# TromboneTutor.net
KiCad netlist of a schematic drawn in EAGLE
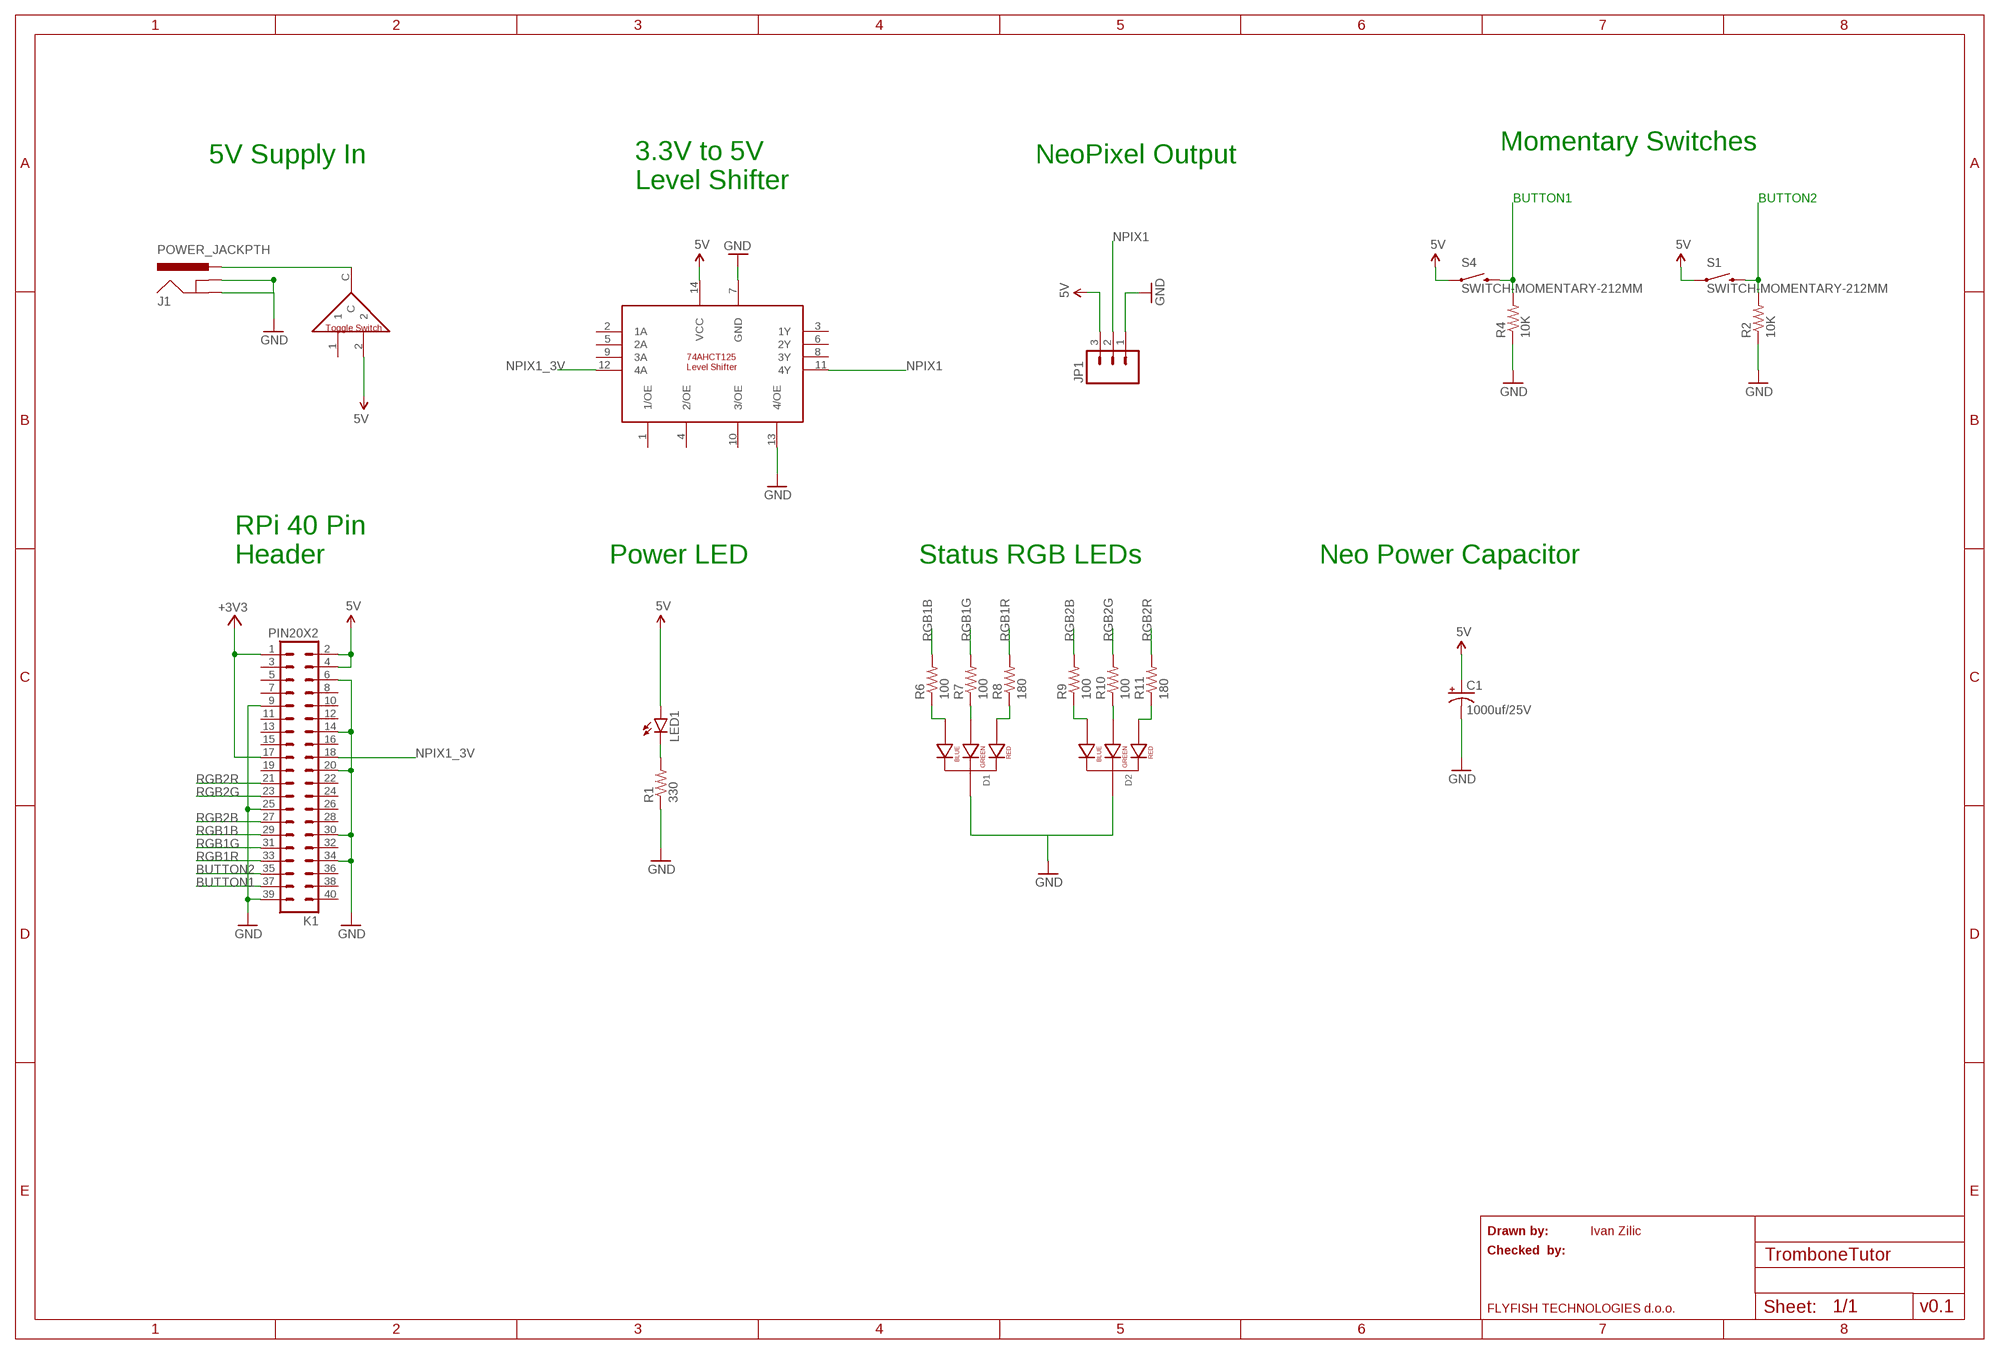
[diagram p0: schematic, sheet 1]

(export (version "E")
  (design (tool "Eeschema 10.0.6"))
  (components
    (comp (ref "C1")
      (value "1000uf/25V")
      (footprint "eagle-import:CPOL-RADIAL-1000UF-25V-KIT")
      (libsource (lib "eagle-import") (part "1000UF-25V(PTH)KIT"))
    )
    (comp (ref "D1")
      (value "LED-RGB-CC-THRUDIFFUSE")
      (footprint "eagle-import:LED-RGB-THRU")
      (libsource (lib "eagle-import") (part "LED-RGB-CC-THRUDIFFUSE"))
    )
    (comp (ref "D2")
      (value "LED-RGB-CC-THRUDIFFUSE")
      (footprint "eagle-import:LED-RGB-THRU")
      (libsource (lib "eagle-import") (part "LED-RGB-CC-THRUDIFFUSE"))
    )
    (comp (ref "J1")
      (value "POWER_JACKPTH")
      (footprint "eagle-import:POWER_JACK_PTH")
      (libsource (lib "eagle-import") (part "POWER_JACKPTH"))
    )
    (comp (ref "JP1")
      (value "M03PTH")
      (footprint "eagle-import:1X03")
      (libsource (lib "eagle-import") (part "M03PTH"))
    )
    (comp (ref "K1")
      (value "PIN20X2")
      (footprint "eagle-import:PIN_20X2")
      (libsource (lib "eagle-import") (part "PIN20X2"))
    )
    (comp (ref "LED1")
      (value "LED5MM")
      (footprint "eagle-import:LED5MM")
      (libsource (lib "eagle-import") (part "LED5MM"))
    )
    (comp (ref "R1")
      (value "330")
      (footprint "eagle-import:AXIAL-0.3")
      (libsource (lib "eagle-import") (part "RESISTORAXIAL-0.3"))
    )
    (comp (ref "R2")
      (value "10K")
      (footprint "eagle-import:AXIAL-0.3-KIT")
      (libsource (lib "eagle-import") (part "RESISTORKIT"))
    )
    (comp (ref "R4")
      (value "10K")
      (footprint "eagle-import:AXIAL-0.3-KIT")
      (libsource (lib "eagle-import") (part "RESISTORKIT"))
    )
    (comp (ref "R6")
      (value "100")
      (footprint "eagle-import:AXIAL-0.3")
      (libsource (lib "eagle-import") (part "RESISTORAXIAL-0.3"))
    )
    (comp (ref "R7")
      (value "100")
      (footprint "eagle-import:AXIAL-0.3")
      (libsource (lib "eagle-import") (part "RESISTORAXIAL-0.3"))
    )
    (comp (ref "R8")
      (value "180")
      (footprint "eagle-import:AXIAL-0.3")
      (libsource (lib "eagle-import") (part "RESISTORAXIAL-0.3"))
    )
    (comp (ref "R9")
      (value "100")
      (footprint "eagle-import:AXIAL-0.3")
      (libsource (lib "eagle-import") (part "RESISTORAXIAL-0.3"))
    )
    (comp (ref "R10")
      (value "100")
      (footprint "eagle-import:AXIAL-0.3")
      (libsource (lib "eagle-import") (part "RESISTORAXIAL-0.3"))
    )
    (comp (ref "R11")
      (value "180")
      (footprint "eagle-import:AXIAL-0.3")
      (libsource (lib "eagle-import") (part "RESISTORAXIAL-0.3"))
    )
    (comp (ref "S1")
      (value "SWITCH-MOMENTARY-212MM")
      (footprint "eagle-import:TACTILE-PTH-12MM")
      (libsource (lib "eagle-import") (part "SWITCH-MOMENTARY-212MM"))
    )
    (comp (ref "S4")
      (value "SWITCH-MOMENTARY-212MM")
      (footprint "eagle-import:TACTILE-PTH-12MM")
      (libsource (lib "eagle-import") (part "SWITCH-MOMENTARY-212MM"))
    )
    (comp (ref "U$1")
      (value "74AHCT125_LEVELSHIFT")
      (footprint "eagle-import:DIL14")
      (libsource (lib "eagle-import") (part "74AHCT125_LEVELSHIFT"))
    )
    (comp (ref "U$2")
      (value "TOGGLE_SWITCH_ESTORE")
      (footprint "eagle-import:TOGGLE_SWITCH_ESTORE")
      (libsource (lib "eagle-import") (part "TOGGLE_SWITCH_ESTORE"))
    )
  )
  (nets
    (net (code "1") (name "+3V3") (class "Default")
      (node (ref "K1") (pin "1") (pinfunction "1_1") (pintype "passive"))
      (node (ref "K1") (pin "17") (pinfunction "17_17") (pintype "passive"))
    )
    (net (code "2") (name "/BUTTON1") (class "Default")
      (node (ref "K1") (pin "37") (pinfunction "37_37") (pintype "passive"))
      (node (ref "R4") (pin "P$2") (pinfunction "2_P$2") (pintype "passive"))
      (node (ref "S4") (pin "3") (pinfunction "2_3") (pintype "passive"))
    )
    (net (code "3") (name "/BUTTON2") (class "Default")
      (node (ref "K1") (pin "35") (pinfunction "35_35") (pintype "passive"))
      (node (ref "R2") (pin "P$2") (pinfunction "2_P$2") (pintype "passive"))
      (node (ref "S1") (pin "3") (pinfunction "2_3") (pintype "passive"))
    )
    (net (code "4") (name "/NPIX1") (class "Default")
      (node (ref "JP1") (pin "2") (pinfunction "2_2") (pintype "passive"))
      (node (ref "U$1") (pin "11") (pinfunction "4Y_11") (pintype "bidirectional"))
    )
    (net (code "5") (name "/NPIX1_3V") (class "Default")
      (node (ref "K1") (pin "18") (pinfunction "18_18") (pintype "passive"))
      (node (ref "U$1") (pin "12") (pinfunction "4A_12") (pintype "bidirectional"))
    )
    (net (code "6") (name "/RGB1B") (class "Default")
      (node (ref "K1") (pin "29") (pinfunction "29_29") (pintype "passive"))
      (node (ref "R6") (pin "P$2") (pinfunction "2_P$2") (pintype "passive"))
    )
    (net (code "7") (name "/RGB1G") (class "Default")
      (node (ref "K1") (pin "31") (pinfunction "31_31") (pintype "passive"))
      (node (ref "R7") (pin "P$2") (pinfunction "2_P$2") (pintype "passive"))
    )
    (net (code "8") (name "/RGB1R") (class "Default")
      (node (ref "K1") (pin "33") (pinfunction "33_33") (pintype "passive"))
      (node (ref "R8") (pin "P$2") (pinfunction "2_P$2") (pintype "passive"))
    )
    (net (code "9") (name "/RGB2B") (class "Default")
      (node (ref "K1") (pin "27") (pinfunction "27_27") (pintype "passive"))
      (node (ref "R9") (pin "P$2") (pinfunction "2_P$2") (pintype "passive"))
    )
    (net (code "10") (name "/RGB2G") (class "Default")
      (node (ref "K1") (pin "23") (pinfunction "23_23") (pintype "passive"))
      (node (ref "R10") (pin "P$2") (pinfunction "2_P$2") (pintype "passive"))
    )
    (net (code "11") (name "/RGB2R") (class "Default")
      (node (ref "K1") (pin "21") (pinfunction "21_21") (pintype "passive"))
      (node (ref "R11") (pin "P$2") (pinfunction "2_P$2") (pintype "passive"))
    )
    (net (code "12") (name "5V") (class "Default")
      (node (ref "C1") (pin "+") (pinfunction "+_+") (pintype "passive"))
      (node (ref "JP1") (pin "3") (pinfunction "3_3") (pintype "passive"))
      (node (ref "K1") (pin "2") (pinfunction "2_2") (pintype "passive"))
      (node (ref "K1") (pin "4") (pinfunction "4_4") (pintype "passive"))
      (node (ref "LED1") (pin "A") (pinfunction "A_A") (pintype "passive"))
      (node (ref "S1") (pin "1") (pinfunction "1_1") (pintype "passive"))
      (node (ref "S4") (pin "1") (pinfunction "1_1") (pintype "passive"))
      (node (ref "U$1") (pin "14") (pinfunction "VCC_14") (pintype "bidirectional"))
      (node (ref "U$2") (pin "2") (pinfunction "2_2") (pintype "bidirectional"))
    )
    (net (code "13") (name "GND") (class "Default")
      (node (ref "C1") (pin "-") (pinfunction "-_-") (pintype "passive"))
      (node (ref "D1") (pin "2") (pinfunction "CATHODE_2") (pintype "bidirectional"))
      (node (ref "D2") (pin "2") (pinfunction "CATHODE_2") (pintype "bidirectional"))
      (node (ref "J1") (pin "GND") (pinfunction "GND_GND") (pintype "bidirectional"))
      (node (ref "J1") (pin "GNDBREAK") (pinfunction "GNDBREAK_GNDBREAK") (pintype "bidirectional"))
      (node (ref "JP1") (pin "1") (pinfunction "1_1") (pintype "passive"))
      (node (ref "K1") (pin "14") (pinfunction "14_14") (pintype "passive"))
      (node (ref "K1") (pin "20") (pinfunction "20_20") (pintype "passive"))
      (node (ref "K1") (pin "25") (pinfunction "25_25") (pintype "passive"))
      (node (ref "K1") (pin "30") (pinfunction "30_30") (pintype "passive"))
      (node (ref "K1") (pin "34") (pinfunction "34_34") (pintype "passive"))
      (node (ref "K1") (pin "39") (pinfunction "39_39") (pintype "passive"))
      (node (ref "K1") (pin "6") (pinfunction "6_6") (pintype "passive"))
      (node (ref "K1") (pin "9") (pinfunction "9_9") (pintype "passive"))
      (node (ref "R1") (pin "P$1") (pinfunction "1_P$1") (pintype "passive"))
      (node (ref "R2") (pin "P$1") (pinfunction "1_P$1") (pintype "passive"))
      (node (ref "R4") (pin "P$1") (pinfunction "1_P$1") (pintype "passive"))
      (node (ref "U$1") (pin "13") (pinfunction "4/OE_13") (pintype "bidirectional"))
      (node (ref "U$1") (pin "7") (pinfunction "GND_7") (pintype "bidirectional"))
    )
    (net (code "14") (name "Net-(D1-BLUE_CATHODE)") (class "Default")
      (node (ref "D1") (pin "4") (pinfunction "BLUE_CATHODE_4") (pintype "bidirectional"))
      (node (ref "R6") (pin "P$1") (pinfunction "1_P$1") (pintype "passive"))
    )
    (net (code "15") (name "Net-(D1-GREEN_CATHODE)") (class "Default")
      (node (ref "D1") (pin "3") (pinfunction "GREEN_CATHODE_3") (pintype "bidirectional"))
      (node (ref "R7") (pin "P$1") (pinfunction "1_P$1") (pintype "passive"))
    )
    (net (code "16") (name "Net-(D1-RED_CATHODE)") (class "Default")
      (node (ref "D1") (pin "1") (pinfunction "RED_CATHODE_1") (pintype "bidirectional"))
      (node (ref "R8") (pin "P$1") (pinfunction "1_P$1") (pintype "passive"))
    )
    (net (code "17") (name "Net-(D2-BLUE_CATHODE)") (class "Default")
      (node (ref "D2") (pin "4") (pinfunction "BLUE_CATHODE_4") (pintype "bidirectional"))
      (node (ref "R9") (pin "P$1") (pinfunction "1_P$1") (pintype "passive"))
    )
    (net (code "18") (name "Net-(D2-GREEN_CATHODE)") (class "Default")
      (node (ref "D2") (pin "3") (pinfunction "GREEN_CATHODE_3") (pintype "bidirectional"))
      (node (ref "R10") (pin "P$1") (pinfunction "1_P$1") (pintype "passive"))
    )
    (net (code "19") (name "Net-(D2-RED_CATHODE)") (class "Default")
      (node (ref "D2") (pin "1") (pinfunction "RED_CATHODE_1") (pintype "bidirectional"))
      (node (ref "R11") (pin "P$1") (pinfunction "1_P$1") (pintype "passive"))
    )
    (net (code "20") (name "Net-(J1-PadPWR)") (class "Default")
      (node (ref "J1") (pin "PWR") (pinfunction "PWR_PWR") (pintype "bidirectional"))
      (node (ref "U$2") (pin "C") (pinfunction "C_C") (pintype "bidirectional"))
    )
    (net (code "21") (name "Net-(LED1-C)") (class "Default")
      (node (ref "LED1") (pin "K") (pinfunction "C_K") (pintype "passive"))
      (node (ref "R1") (pin "P$2") (pinfunction "2_P$2") (pintype "passive"))
    )
    (net (code "22") (name "unconnected-(K1-Pad3)") (class "Default")
      (node (ref "K1") (pin "3") (pinfunction "3_3") (pintype "passive"))
    )
    (net (code "23") (name "unconnected-(K1-Pad5)") (class "Default")
      (node (ref "K1") (pin "5") (pinfunction "5_5") (pintype "passive"))
    )
    (net (code "24") (name "unconnected-(K1-Pad7)") (class "Default")
      (node (ref "K1") (pin "7") (pinfunction "7_7") (pintype "passive"))
    )
    (net (code "25") (name "unconnected-(K1-Pad8)") (class "Default")
      (node (ref "K1") (pin "8") (pinfunction "8_8") (pintype "passive"))
    )
    (net (code "26") (name "unconnected-(K1-Pad10)") (class "Default")
      (node (ref "K1") (pin "10") (pinfunction "10_10") (pintype "passive"))
    )
    (net (code "27") (name "unconnected-(K1-Pad11)") (class "Default")
      (node (ref "K1") (pin "11") (pinfunction "11_11") (pintype "passive"))
    )
    (net (code "28") (name "unconnected-(K1-Pad12)") (class "Default")
      (node (ref "K1") (pin "12") (pinfunction "12_12") (pintype "passive"))
    )
    (net (code "29") (name "unconnected-(K1-Pad13)") (class "Default")
      (node (ref "K1") (pin "13") (pinfunction "13_13") (pintype "passive"))
    )
    (net (code "30") (name "unconnected-(K1-Pad15)") (class "Default")
      (node (ref "K1") (pin "15") (pinfunction "15_15") (pintype "passive"))
    )
    (net (code "31") (name "unconnected-(K1-Pad16)") (class "Default")
      (node (ref "K1") (pin "16") (pinfunction "16_16") (pintype "passive"))
    )
    (net (code "32") (name "unconnected-(K1-Pad19)") (class "Default")
      (node (ref "K1") (pin "19") (pinfunction "19_19") (pintype "passive"))
    )
    (net (code "33") (name "unconnected-(K1-Pad22)") (class "Default")
      (node (ref "K1") (pin "22") (pinfunction "22_22") (pintype "passive"))
    )
    (net (code "34") (name "unconnected-(K1-Pad24)") (class "Default")
      (node (ref "K1") (pin "24") (pinfunction "24_24") (pintype "passive"))
    )
    (net (code "35") (name "unconnected-(K1-Pad26)") (class "Default")
      (node (ref "K1") (pin "26") (pinfunction "26_26") (pintype "passive"))
    )
    (net (code "36") (name "unconnected-(K1-Pad28)") (class "Default")
      (node (ref "K1") (pin "28") (pinfunction "28_28") (pintype "passive"))
    )
    (net (code "37") (name "unconnected-(K1-Pad32)") (class "Default")
      (node (ref "K1") (pin "32") (pinfunction "32_32") (pintype "passive"))
    )
    (net (code "38") (name "unconnected-(K1-Pad36)") (class "Default")
      (node (ref "K1") (pin "36") (pinfunction "36_36") (pintype "passive"))
    )
    (net (code "39") (name "unconnected-(K1-Pad38)") (class "Default")
      (node (ref "K1") (pin "38") (pinfunction "38_38") (pintype "passive"))
    )
    (net (code "40") (name "unconnected-(K1-Pad40)") (class "Default")
      (node (ref "K1") (pin "40") (pinfunction "40_40") (pintype "passive"))
    )
    (net (code "41") (name "unconnected-(U$1-1A-Pad2)") (class "Default")
      (node (ref "U$1") (pin "2") (pinfunction "1A_2") (pintype "bidirectional"))
    )
    (net (code "42") (name "unconnected-(U$1-1Y-Pad3)") (class "Default")
      (node (ref "U$1") (pin "3") (pinfunction "1Y_3") (pintype "bidirectional"))
    )
    (net (code "43") (name "unconnected-(U$1-1{slash}OE-Pad1)") (class "Default")
      (node (ref "U$1") (pin "1") (pinfunction "1/OE_1") (pintype "bidirectional"))
    )
    (net (code "44") (name "unconnected-(U$1-2A-Pad5)") (class "Default")
      (node (ref "U$1") (pin "5") (pinfunction "2A_5") (pintype "bidirectional"))
    )
    (net (code "45") (name "unconnected-(U$1-2Y-Pad6)") (class "Default")
      (node (ref "U$1") (pin "6") (pinfunction "2Y_6") (pintype "bidirectional"))
    )
    (net (code "46") (name "unconnected-(U$1-2{slash}OE-Pad4)") (class "Default")
      (node (ref "U$1") (pin "4") (pinfunction "2/OE_4") (pintype "bidirectional"))
    )
    (net (code "47") (name "unconnected-(U$1-3A-Pad9)") (class "Default")
      (node (ref "U$1") (pin "9") (pinfunction "3A_9") (pintype "bidirectional"))
    )
    (net (code "48") (name "unconnected-(U$1-3Y-Pad8)") (class "Default")
      (node (ref "U$1") (pin "8") (pinfunction "3Y_8") (pintype "bidirectional"))
    )
    (net (code "49") (name "unconnected-(U$1-3{slash}OE-Pad10)") (class "Default")
      (node (ref "U$1") (pin "10") (pinfunction "3/OE_10") (pintype "bidirectional"))
    )
    (net (code "50") (name "unconnected-(U$2-Pad1)") (class "Default")
      (node (ref "U$2") (pin "1") (pinfunction "1_1") (pintype "bidirectional"))
    )
  )
)
